# untitled.net
KiCad netlist of a schematic drawn in EAGLE
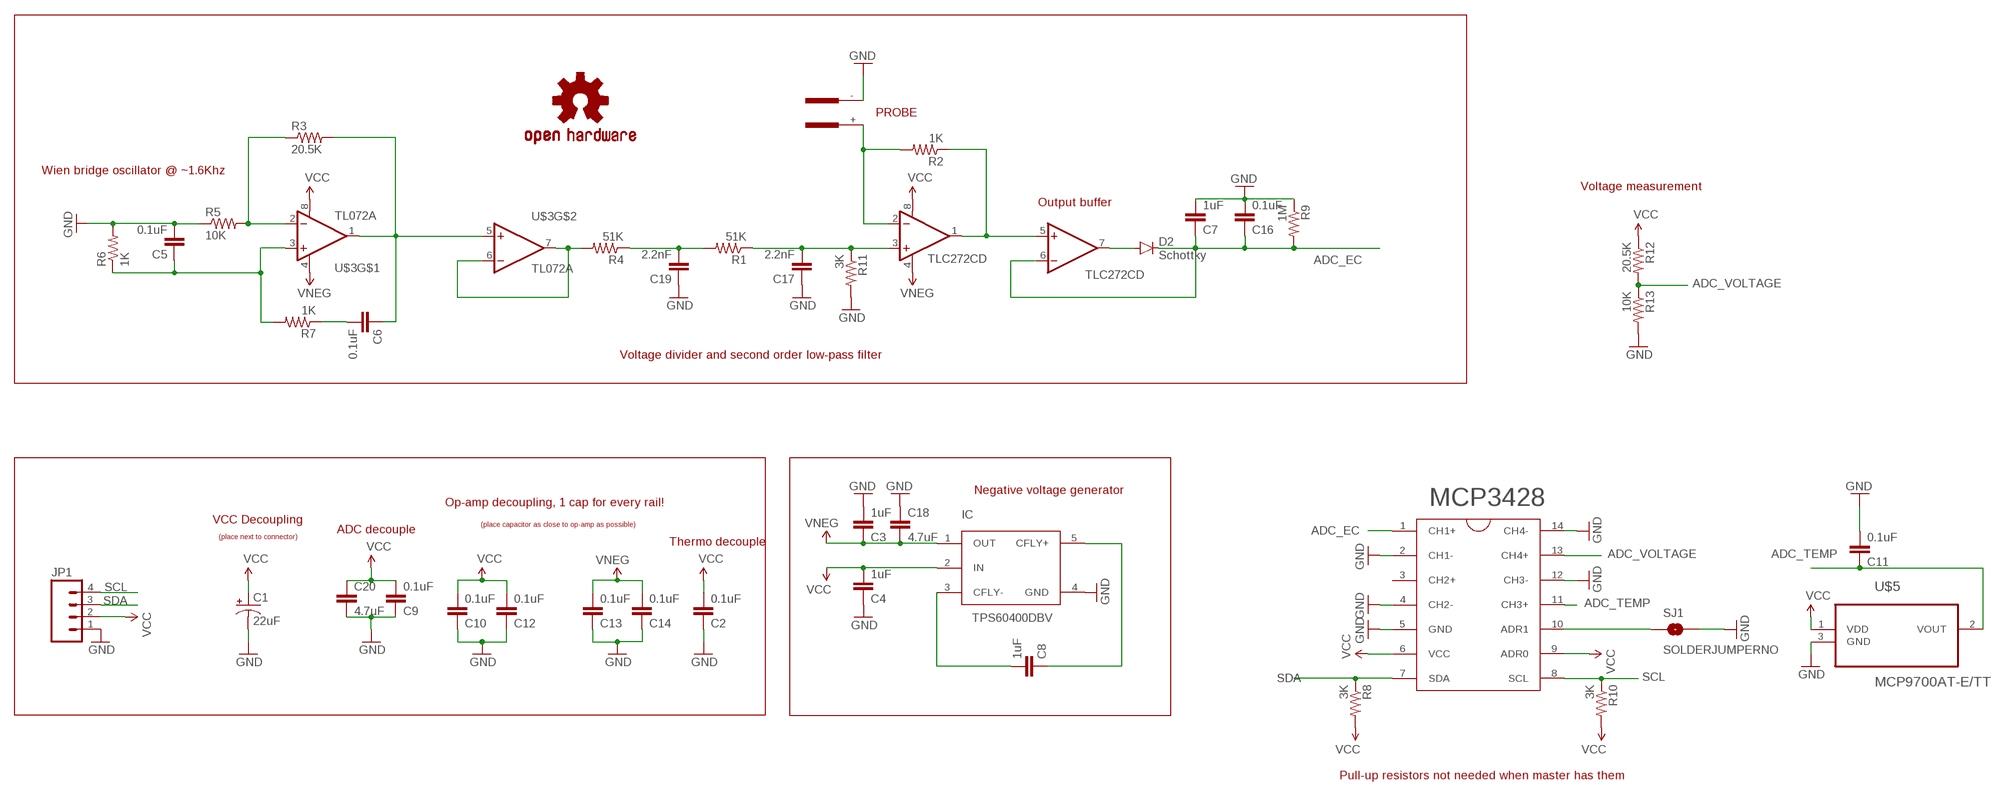
[diagram p0: schematic, sheet 1]

(export (version "E")
  (design (tool "Eeschema 10.0.6"))
  (components
    (comp (ref "C1")
      (value "22uF")
      (footprint "eagle-import:EIA3216")
      (libsource (lib "eagle-import") (part "10UF-TANT"))
    )
    (comp (ref "C2")
      (value "0.1uF")
      (footprint "eagle-import:0603-CAP")
      (libsource (lib "eagle-import") (part "CAP0603-CAP"))
    )
    (comp (ref "C3")
      (value "1uF")
      (footprint "eagle-import:0603-CAP")
      (libsource (lib "eagle-import") (part "CAP0603-CAP"))
    )
    (comp (ref "C4")
      (value "1uF")
      (footprint "eagle-import:0603-CAP")
      (libsource (lib "eagle-import") (part "CAP0603-CAP"))
    )
    (comp (ref "C5")
      (value "0.1uF")
      (footprint "eagle-import:0603-CAP")
      (libsource (lib "eagle-import") (part "CAP0603-CAP"))
    )
    (comp (ref "C6")
      (value "0.1uF")
      (footprint "eagle-import:0603-CAP")
      (libsource (lib "eagle-import") (part "CAP0603-CAP"))
    )
    (comp (ref "C7")
      (value "1uF")
      (footprint "eagle-import:0603-CAP")
      (libsource (lib "eagle-import") (part "CAP0603-CAP"))
    )
    (comp (ref "C8")
      (value "1uF")
      (footprint "eagle-import:0603-CAP")
      (libsource (lib "eagle-import") (part "CAP0603-CAP"))
    )
    (comp (ref "C9")
      (value "0.1uF")
      (footprint "eagle-import:0603-CAP")
      (libsource (lib "eagle-import") (part "CAP0603-CAP"))
    )
    (comp (ref "C10")
      (value "0.1uF")
      (footprint "eagle-import:0603-CAP")
      (libsource (lib "eagle-import") (part "CAP0603-CAP"))
    )
    (comp (ref "C11")
      (value "0.1uF")
      (footprint "eagle-import:0603-CAP")
      (libsource (lib "eagle-import") (part "CAP0603-CAP"))
    )
    (comp (ref "C12")
      (value "0.1uF")
      (footprint "eagle-import:0603-CAP")
      (libsource (lib "eagle-import") (part "CAP0603-CAP"))
    )
    (comp (ref "C13")
      (value "0.1uF")
      (footprint "eagle-import:0603-CAP")
      (libsource (lib "eagle-import") (part "CAP0603-CAP"))
    )
    (comp (ref "C14")
      (value "0.1uF")
      (footprint "eagle-import:0603-CAP")
      (libsource (lib "eagle-import") (part "CAP0603-CAP"))
    )
    (comp (ref "C16")
      (value "0.1uF")
      (footprint "eagle-import:0603-CAP")
      (libsource (lib "eagle-import") (part "CAP0603-CAP"))
    )
    (comp (ref "C17")
      (value "2.2nF")
      (footprint "eagle-import:0603-CAP")
      (libsource (lib "eagle-import") (part "CAP0603-CAP"))
    )
    (comp (ref "C18")
      (value "4.7uF")
      (footprint "eagle-import:0805")
      (libsource (lib "eagle-import") (part "CAP0805"))
    )
    (comp (ref "C19")
      (value "2.2nF")
      (footprint "eagle-import:0603-CAP")
      (libsource (lib "eagle-import") (part "CAP0603-CAP"))
    )
    (comp (ref "C20")
      (value "4.7uF")
      (footprint "eagle-import:0805")
      (libsource (lib "eagle-import") (part "CAP0805"))
    )
    (comp (ref "D2")
      (value "Schottky")
      (footprint "eagle-import:SOD-323")
      (libsource (lib "eagle-import") (part "DIODESOD"))
    )
    (comp (ref "IC")
      (value "TPS60400DBV")
      (footprint "eagle-import:SOT23-5")
      (libsource (lib "eagle-import") (part "TPS60400DBV"))
    )
    (comp (ref "JP1")
      (value "M04LONGPADS")
      (footprint "eagle-import:1X04_LONGPADS")
      (libsource (lib "eagle-import") (part "M04LONGPADS"))
    )
    (comp (ref "LOGO1")
      (value "OSHW-LOGOM")
      (footprint "eagle-import:OSHW-LOGO-M")
      (libsource (lib "eagle-import") (part "OSHW-LOGOM"))
    )
    (comp (ref "MCP3428")
      (value "MCP3428")
      (footprint "eagle-import:SO14")
      (libsource (lib "eagle-import") (part "MCP3428"))
    )
    (comp (ref "R1")
      (value "51K")
      (footprint "eagle-import:0603-RES")
      (libsource (lib "eagle-import") (part "1K-1%"))
    )
    (comp (ref "R2")
      (value "1K")
      (footprint "eagle-import:0603-RES")
      (libsource (lib "eagle-import") (part "1K-1%"))
    )
    (comp (ref "R3")
      (value "20.5K")
      (footprint "eagle-import:0603-RES")
      (libsource (lib "eagle-import") (part "22KOHM1/10W1%(0603)"))
    )
    (comp (ref "R4")
      (value "51K")
      (footprint "eagle-import:0603-RES")
      (libsource (lib "eagle-import") (part "1K-1%"))
    )
    (comp (ref "R5")
      (value "10K")
      (footprint "eagle-import:0603-RES")
      (libsource (lib "eagle-import") (part "10K-1%RES-00824"))
    )
    (comp (ref "R6")
      (value "1K")
      (footprint "eagle-import:0603-RES")
      (libsource (lib "eagle-import") (part "1K-1%"))
    )
    (comp (ref "R7")
      (value "1K")
      (footprint "eagle-import:0603-RES")
      (libsource (lib "eagle-import") (part "1K-1%"))
    )
    (comp (ref "R8")
      (value "3K")
      (footprint "eagle-import:0603-RES")
      (libsource (lib "eagle-import") (part "10K-1%RES-00824"))
    )
    (comp (ref "R9")
      (value "1M")
      (footprint "eagle-import:0603-RES")
      (libsource (lib "eagle-import") (part "10K-1%RES-00824"))
    )
    (comp (ref "R10")
      (value "3K")
      (footprint "eagle-import:0603-RES")
      (libsource (lib "eagle-import") (part "10K-1%RES-00824"))
    )
    (comp (ref "R11")
      (value "3K")
      (footprint "eagle-import:0603-RES")
      (libsource (lib "eagle-import") (part "1K-1%"))
    )
    (comp (ref "R12")
      (value "20.5K")
      (footprint "eagle-import:0603-RES")
      (libsource (lib "eagle-import") (part "1K-1%"))
    )
    (comp (ref "R13")
      (value "10K")
      (footprint "eagle-import:0603-RES")
      (libsource (lib "eagle-import") (part "1K-1%"))
    )
    (comp (ref "SJ1")
      (value "SOLDERJUMPERNO")
      (footprint "eagle-import:SJ_2S-NO")
      (libsource (lib "eagle-import") (part "SOLDERJUMPERNO"))
    )
    (comp (ref "U$1")
      (value "TLC272CD")
      (footprint "eagle-import:SOIC8")
      (libsource (lib "eagle-import") (part "TL072A"))
    )
    (comp (ref "U$2")
      (value "K1-PROBE")
      (footprint "eagle-import:K1-PROBE")
      (libsource (lib "eagle-import") (part "K1-PROBE"))
    )
    (comp (ref "U$3")
      (value "TL072A")
      (footprint "eagle-import:SOIC8")
      (libsource (lib "eagle-import") (part "TL072A"))
    )
    (comp (ref "U$5")
      (value "MCP9700AT-E/TT")
      (footprint "eagle-import:SOT95P237X112-3N")
      (libsource (lib "eagle-import") (part "MCP9700AT-E/TT"))
    )
  )
  (nets
    (net (code "1") (name "/ADC_EC") (class "Default")
      (node (ref "C16") (pin "1") (pinfunction "1_1") (pintype "passive"))
      (node (ref "C7") (pin "1") (pinfunction "1_1") (pintype "passive"))
      (node (ref "D2") (pin "C") (pinfunction "C_C") (pintype "passive"))
      (node (ref "MCP3428") (pin "1") (pinfunction "CH1+_1") (pintype "bidirectional"))
      (node (ref "R9") (pin "2") (pinfunction "2_2") (pintype "passive"))
      (node (ref "U$1") (pin "6") (pinfunction "-IN_6") (pintype "input"))
    )
    (net (code "2") (name "/ADC_TEMP") (class "Default")
      (node (ref "C11") (pin "1") (pinfunction "1_1") (pintype "passive"))
      (node (ref "MCP3428") (pin "11") (pinfunction "CH3+_11") (pintype "bidirectional"))
      (node (ref "U$5") (pin "2") (pinfunction "VOUT_2") (pintype "output"))
    )
    (net (code "3") (name "/ADC_VOLTAGE") (class "Default")
      (node (ref "MCP3428") (pin "13") (pinfunction "CH4+_13") (pintype "bidirectional"))
      (node (ref "R12") (pin "2") (pinfunction "2_2") (pintype "passive"))
      (node (ref "R13") (pin "1") (pinfunction "1_1") (pintype "passive"))
    )
    (net (code "4") (name "/SCL") (class "Default")
      (node (ref "JP1") (pin "4") (pinfunction "4_4") (pintype "passive"))
      (node (ref "MCP3428") (pin "8") (pinfunction "SCL_8") (pintype "bidirectional"))
      (node (ref "R10") (pin "1") (pinfunction "1_1") (pintype "passive"))
    )
    (net (code "5") (name "/SDA") (class "Default")
      (node (ref "JP1") (pin "3") (pinfunction "3_3") (pintype "passive"))
      (node (ref "MCP3428") (pin "7") (pinfunction "SDA_7") (pintype "bidirectional"))
      (node (ref "R8") (pin "1") (pinfunction "1_1") (pintype "passive"))
    )
    (net (code "6") (name "GND") (class "Default")
      (node (ref "C1") (pin "C") (pinfunction "-_C") (pintype "passive"))
      (node (ref "C10") (pin "1") (pinfunction "1_1") (pintype "passive"))
      (node (ref "C11") (pin "2") (pinfunction "2_2") (pintype "passive"))
      (node (ref "C12") (pin "1") (pinfunction "1_1") (pintype "passive"))
      (node (ref "C13") (pin "1") (pinfunction "1_1") (pintype "passive"))
      (node (ref "C14") (pin "1") (pinfunction "1_1") (pintype "passive"))
      (node (ref "C16") (pin "2") (pinfunction "2_2") (pintype "passive"))
      (node (ref "C17") (pin "1") (pinfunction "1_1") (pintype "passive"))
      (node (ref "C18") (pin "1") (pinfunction "1_1") (pintype "passive"))
      (node (ref "C19") (pin "1") (pinfunction "1_1") (pintype "passive"))
      (node (ref "C2") (pin "1") (pinfunction "1_1") (pintype "passive"))
      (node (ref "C20") (pin "2") (pinfunction "2_2") (pintype "passive"))
      (node (ref "C3") (pin "2") (pinfunction "2_2") (pintype "passive"))
      (node (ref "C4") (pin "1") (pinfunction "1_1") (pintype "passive"))
      (node (ref "C5") (pin "2") (pinfunction "2_2") (pintype "passive"))
      (node (ref "C7") (pin "2") (pinfunction "2_2") (pintype "passive"))
      (node (ref "C9") (pin "1") (pinfunction "1_1") (pintype "passive"))
      (node (ref "IC") (pin "4") (pinfunction "GND_4") (pintype "bidirectional"))
      (node (ref "JP1") (pin "1") (pinfunction "1_1") (pintype "passive"))
      (node (ref "MCP3428") (pin "12") (pinfunction "CH3-_12") (pintype "bidirectional"))
      (node (ref "MCP3428") (pin "14") (pinfunction "CH4-_14") (pintype "bidirectional"))
      (node (ref "MCP3428") (pin "2") (pinfunction "CH1-_2") (pintype "bidirectional"))
      (node (ref "MCP3428") (pin "4") (pinfunction "CH2-_4") (pintype "bidirectional"))
      (node (ref "MCP3428") (pin "5") (pinfunction "GND_5") (pintype "bidirectional"))
      (node (ref "R11") (pin "2") (pinfunction "2_2") (pintype "passive"))
      (node (ref "R13") (pin "2") (pinfunction "2_2") (pintype "passive"))
      (node (ref "R5") (pin "1") (pinfunction "1_1") (pintype "passive"))
      (node (ref "R6") (pin "2") (pinfunction "2_2") (pintype "passive"))
      (node (ref "R9") (pin "1") (pinfunction "1_1") (pintype "passive"))
      (node (ref "SJ1") (pin "2") (pinfunction "2_2") (pintype "passive"))
      (node (ref "U$2") (pin "-") (pinfunction "P$2_-") (pintype "bidirectional"))
      (node (ref "U$5") (pin "3") (pinfunction "GND_3") (pintype "passive"))
    )
    (net (code "7") (name "Net-(C6-Pad2)") (class "Default")
      (node (ref "C6") (pin "2") (pinfunction "2_2") (pintype "passive"))
      (node (ref "R7") (pin "1") (pinfunction "1_1") (pintype "passive"))
    )
    (net (code "8") (name "Net-(C19-Pad2)") (class "Default")
      (node (ref "C19") (pin "2") (pinfunction "2_2") (pintype "passive"))
      (node (ref "R1") (pin "2") (pinfunction "2_2") (pintype "passive"))
      (node (ref "R4") (pin "1") (pinfunction "1_1") (pintype "passive"))
    )
    (net (code "9") (name "Net-(IC-CFLY+)") (class "Default")
      (node (ref "C8") (pin "1") (pinfunction "1_1") (pintype "passive"))
      (node (ref "IC") (pin "5") (pinfunction "CFLY+_5") (pintype "bidirectional"))
    )
    (net (code "10") (name "Net-(IC-CFLY-)") (class "Default")
      (node (ref "C8") (pin "2") (pinfunction "2_2") (pintype "passive"))
      (node (ref "IC") (pin "3") (pinfunction "CFLY-_3") (pintype "bidirectional"))
    )
    (net (code "11") (name "Net-(MCP3428-ADR1)") (class "Default")
      (node (ref "MCP3428") (pin "10") (pinfunction "ADR1_10") (pintype "bidirectional"))
      (node (ref "SJ1") (pin "1") (pinfunction "1_1") (pintype "passive"))
    )
    (net (code "12") (name "Net-(U$1A-+IN)") (class "Default")
      (node (ref "C17") (pin "2") (pinfunction "2_2") (pintype "passive"))
      (node (ref "R1") (pin "1") (pinfunction "1_1") (pintype "passive"))
      (node (ref "R11") (pin "1") (pinfunction "1_1") (pintype "passive"))
      (node (ref "U$1") (pin "3") (pinfunction "+IN_3") (pintype "input"))
    )
    (net (code "13") (name "Net-(U$1A--IN)") (class "Default")
      (node (ref "R2") (pin "2") (pinfunction "2_2") (pintype "passive"))
      (node (ref "U$1") (pin "2") (pinfunction "-IN_2") (pintype "input"))
      (node (ref "U$2") (pin "+") (pinfunction "P$1_+") (pintype "bidirectional"))
    )
    (net (code "14") (name "Net-(U$1A-OUT)") (class "Default")
      (node (ref "R2") (pin "1") (pinfunction "1_1") (pintype "passive"))
      (node (ref "U$1") (pin "1") (pinfunction "OUT_1") (pintype "output"))
      (node (ref "U$1") (pin "5") (pinfunction "+IN_5") (pintype "input"))
    )
    (net (code "15") (name "Net-(U$1B-OUT)") (class "Default")
      (node (ref "D2") (pin "A") (pinfunction "A_A") (pintype "passive"))
      (node (ref "U$1") (pin "7") (pinfunction "OUT_7") (pintype "output"))
    )
    (net (code "16") (name "Net-(U$3A-+IN)") (class "Default")
      (node (ref "C5") (pin "1") (pinfunction "1_1") (pintype "passive"))
      (node (ref "R6") (pin "1") (pinfunction "1_1") (pintype "passive"))
      (node (ref "R7") (pin "2") (pinfunction "2_2") (pintype "passive"))
      (node (ref "U$3") (pin "3") (pinfunction "+IN_3") (pintype "input"))
    )
    (net (code "17") (name "Net-(U$3A--IN)") (class "Default")
      (node (ref "R3") (pin "1") (pinfunction "1_1") (pintype "passive"))
      (node (ref "R5") (pin "2") (pinfunction "2_2") (pintype "passive"))
      (node (ref "U$3") (pin "2") (pinfunction "-IN_2") (pintype "input"))
    )
    (net (code "18") (name "Net-(U$3A-OUT)") (class "Default")
      (node (ref "C6") (pin "1") (pinfunction "1_1") (pintype "passive"))
      (node (ref "R3") (pin "2") (pinfunction "2_2") (pintype "passive"))
      (node (ref "U$3") (pin "1") (pinfunction "OUT_1") (pintype "output"))
      (node (ref "U$3") (pin "5") (pinfunction "+IN_5") (pintype "input"))
    )
    (net (code "19") (name "Net-(U$3B--IN)") (class "Default")
      (node (ref "R4") (pin "2") (pinfunction "2_2") (pintype "passive"))
      (node (ref "U$3") (pin "6") (pinfunction "-IN_6") (pintype "input"))
      (node (ref "U$3") (pin "7") (pinfunction "OUT_7") (pintype "output"))
    )
    (net (code "20") (name "VCC") (class "Default")
      (node (ref "C1") (pin "A") (pinfunction "+_A") (pintype "passive"))
      (node (ref "C10") (pin "2") (pinfunction "2_2") (pintype "passive"))
      (node (ref "C12") (pin "2") (pinfunction "2_2") (pintype "passive"))
      (node (ref "C2") (pin "2") (pinfunction "2_2") (pintype "passive"))
      (node (ref "C20") (pin "1") (pinfunction "1_1") (pintype "passive"))
      (node (ref "C4") (pin "2") (pinfunction "2_2") (pintype "passive"))
      (node (ref "C9") (pin "2") (pinfunction "2_2") (pintype "passive"))
      (node (ref "IC") (pin "2") (pinfunction "IN_2") (pintype "bidirectional"))
      (node (ref "JP1") (pin "2") (pinfunction "2_2") (pintype "passive"))
      (node (ref "MCP3428") (pin "6") (pinfunction "VCC_6") (pintype "bidirectional"))
      (node (ref "MCP3428") (pin "9") (pinfunction "ADR0_9") (pintype "bidirectional"))
      (node (ref "R10") (pin "2") (pinfunction "2_2") (pintype "passive"))
      (node (ref "R12") (pin "1") (pinfunction "1_1") (pintype "passive"))
      (node (ref "R8") (pin "2") (pinfunction "2_2") (pintype "passive"))
      (node (ref "U$1") (pin "8") (pinfunction "V+_8") (pintype "power_in"))
      (node (ref "U$3") (pin "8") (pinfunction "V+_8") (pintype "power_in"))
      (node (ref "U$5") (pin "1") (pinfunction "VDD_1") (pintype "power_in"))
    )
    (net (code "21") (name "VNEG") (class "Default")
      (node (ref "C13") (pin "2") (pinfunction "2_2") (pintype "passive"))
      (node (ref "C14") (pin "2") (pinfunction "2_2") (pintype "passive"))
      (node (ref "C18") (pin "2") (pinfunction "2_2") (pintype "passive"))
      (node (ref "C3") (pin "1") (pinfunction "1_1") (pintype "passive"))
      (node (ref "IC") (pin "1") (pinfunction "OUT_1") (pintype "bidirectional"))
      (node (ref "U$1") (pin "4") (pinfunction "V-_4") (pintype "power_in"))
      (node (ref "U$3") (pin "4") (pinfunction "V-_4") (pintype "power_in"))
    )
    (net (code "22") (name "unconnected-(MCP3428-CH2+-Pad3)") (class "Default")
      (node (ref "MCP3428") (pin "3") (pinfunction "CH2+_3") (pintype "bidirectional"))
    )
  )
)
